# Sub_MCU.net
KiCad netlist of a schematic drawn in Altium Designer
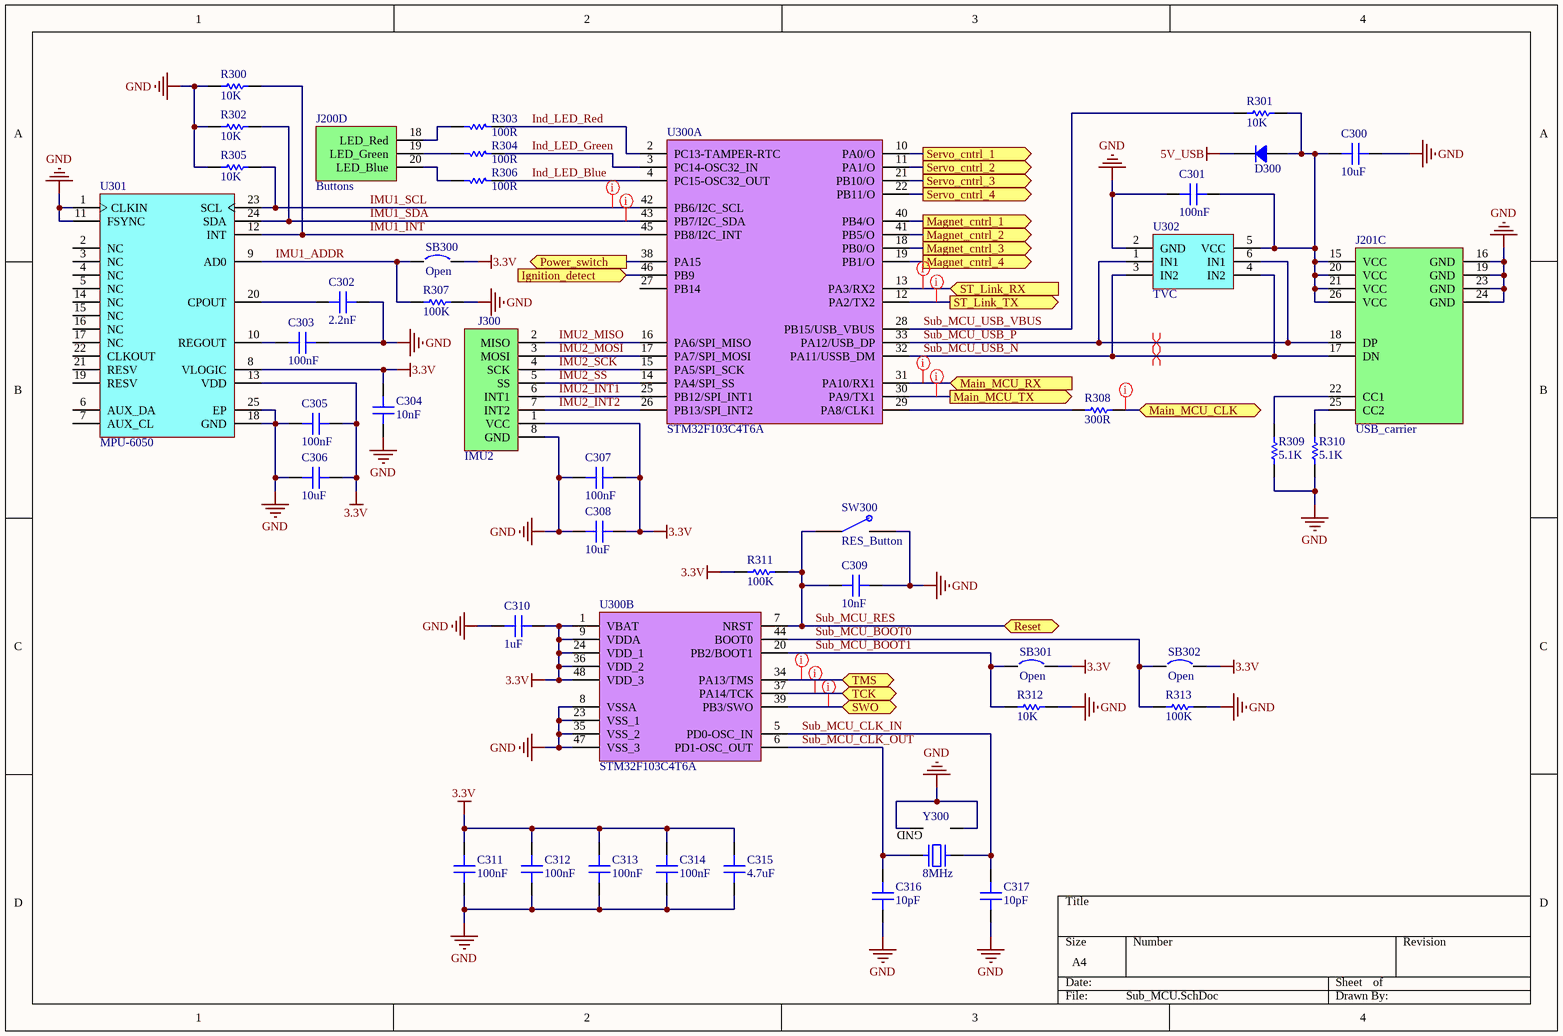
[diagram p0: Sub_MCU.SchDoc]

(export (version "E")
  (design (tool "Eeschema 10.0.6"))
  (components
    (comp (ref "C300")
      (value "10uF")
      (footprint "CAP 0603")
      (description "SMT Capacitor")
      (libsource (lib "Schlib1") (part "Capacitor"))
    )
    (comp (ref "C301")
      (value "100nF")
      (footprint "CAP 0603")
      (description "SMT Capacitor")
      (libsource (lib "Schlib1") (part "Capacitor"))
    )
    (comp (ref "C302")
      (value "2.2nF")
      (footprint "CAP 0603")
      (description "SMT Capacitor")
      (libsource (lib "Schlib1") (part "Capacitor"))
    )
    (comp (ref "C303")
      (value "100nF")
      (footprint "CAP 0603")
      (description "SMT Capacitor")
      (libsource (lib "Schlib1") (part "Capacitor"))
    )
    (comp (ref "C304")
      (value "10nF")
      (footprint "CAP 0603")
      (description "SMT Capacitor")
      (libsource (lib "Schlib1") (part "Capacitor"))
    )
    (comp (ref "C305")
      (value "100nF")
      (footprint "CAP 0603")
      (description "SMT Capacitor")
      (libsource (lib "Schlib1") (part "Capacitor"))
    )
    (comp (ref "C306")
      (value "10uF")
      (footprint "CAP 0603")
      (description "SMT Capacitor")
      (libsource (lib "Schlib1") (part "Capacitor"))
    )
    (comp (ref "C307")
      (value "100nF")
      (footprint "CAP 0603")
      (description "SMT Capacitor")
      (libsource (lib "Schlib1") (part "Capacitor"))
    )
    (comp (ref "C308")
      (value "10uF")
      (footprint "CAP 0603")
      (description "SMT Capacitor")
      (libsource (lib "Schlib1") (part "Capacitor"))
    )
    (comp (ref "C309")
      (value "10nF")
      (footprint "CAP 0603")
      (description "SMT Capacitor")
      (libsource (lib "Schlib1") (part "Capacitor"))
    )
    (comp (ref "C310")
      (value "1uF")
      (footprint "CAP 0603")
      (description "SMT Capacitor")
      (libsource (lib "Schlib1") (part "Capacitor"))
    )
    (comp (ref "C311")
      (value "100nF")
      (footprint "CAP 0603")
      (description "SMT Capacitor")
      (libsource (lib "Schlib1") (part "Capacitor"))
    )
    (comp (ref "C312")
      (value "100nF")
      (footprint "CAP 0603")
      (description "SMT Capacitor")
      (libsource (lib "Schlib1") (part "Capacitor"))
    )
    (comp (ref "C313")
      (value "100nF")
      (footprint "CAP 0603")
      (description "SMT Capacitor")
      (libsource (lib "Schlib1") (part "Capacitor"))
    )
    (comp (ref "C314")
      (value "100nF")
      (footprint "CAP 0603")
      (description "SMT Capacitor")
      (libsource (lib "Schlib1") (part "Capacitor"))
    )
    (comp (ref "C315")
      (value "4.7uF")
      (footprint "CAP 1206")
      (description "SMT Capacitor")
      (libsource (lib "Schlib1") (part "Capacitor"))
    )
    (comp (ref "C316")
      (value "10pF")
      (footprint "CAP 0603")
      (description "SMT Capacitor")
      (libsource (lib "Schlib1") (part "Capacitor"))
    )
    (comp (ref "C317")
      (value "10pF")
      (footprint "CAP 0603")
      (description "SMT Capacitor")
      (libsource (lib "Schlib1") (part "Capacitor"))
    )
    (comp (ref "D300")
      (value "~")
      (footprint "Bourns DO214AC SMA - duplicate")
      (description "Rectifier Diode")
      (libsource (lib "Schlib1") (part "Diode"))
    )
    (comp (ref "J200")
      (value "Buttons")
      (footprint "2167010409")
      (libsource (lib "Schlib1") (part "AUX_carrier"))
    )
    (comp (ref "J201")
      (value "USB_carrier")
      (footprint "2167010409")
      (libsource (lib "Schlib1") (part "USB_carrier"))
    )
    (comp (ref "J300")
      (value "IMU2")
      (footprint "SAMTEC_DWM-08-X-X-S-X")
      (libsource (lib "Schlib1") (part "IMU_connector"))
    )
    (comp (ref "R300")
      (value "10K")
      (footprint "RES 0603")
      (description "Resistor")
      (fields (field (name "PUBLISHER") "Altium Limited"))
      (libsource (lib "Schlib1") (part "Res"))
    )
    (comp (ref "R301")
      (value "10K")
      (footprint "RES 0603")
      (description "Resistor")
      (fields (field (name "PUBLISHER") "Altium Limited"))
      (libsource (lib "Schlib1") (part "Res"))
    )
    (comp (ref "R302")
      (value "10K")
      (footprint "RES 0603")
      (description "Resistor")
      (fields (field (name "PUBLISHER") "Altium Limited"))
      (libsource (lib "Schlib1") (part "Res"))
    )
    (comp (ref "R303")
      (value "100R")
      (footprint "RES 0603")
      (description "Resistor")
      (fields (field (name "PUBLISHER") "Altium Limited"))
      (libsource (lib "Schlib1") (part "Res"))
    )
    (comp (ref "R304")
      (value "100R")
      (footprint "RES 0603")
      (description "Resistor")
      (fields (field (name "PUBLISHER") "Altium Limited"))
      (libsource (lib "Schlib1") (part "Res"))
    )
    (comp (ref "R305")
      (value "10K")
      (footprint "RES 0603")
      (description "Resistor")
      (fields (field (name "PUBLISHER") "Altium Limited"))
      (libsource (lib "Schlib1") (part "Res"))
    )
    (comp (ref "R306")
      (value "100R")
      (footprint "RES 0603")
      (description "Resistor")
      (fields (field (name "PUBLISHER") "Altium Limited"))
      (libsource (lib "Schlib1") (part "Res"))
    )
    (comp (ref "R307")
      (value "100K")
      (footprint "RES 0603")
      (description "Resistor")
      (fields (field (name "PUBLISHER") "Altium Limited"))
      (libsource (lib "Schlib1") (part "Res"))
    )
    (comp (ref "R308")
      (value "300R")
      (footprint "RES 0603")
      (description "Resistor")
      (fields (field (name "PUBLISHER") "Altium Limited"))
      (libsource (lib "Schlib1") (part "Res"))
    )
    (comp (ref "R309")
      (value "5.1K")
      (footprint "RES 0603")
      (description "Resistor")
      (fields (field (name "PUBLISHER") "Altium Limited"))
      (libsource (lib "Schlib1") (part "Res"))
    )
    (comp (ref "R310")
      (value "5.1K")
      (footprint "RES 0603")
      (description "Resistor")
      (fields (field (name "PUBLISHER") "Altium Limited"))
      (libsource (lib "Schlib1") (part "Res"))
    )
    (comp (ref "R311")
      (value "100K")
      (footprint "RES 0603")
      (description "Resistor")
      (fields (field (name "PUBLISHER") "Altium Limited"))
      (libsource (lib "Schlib1") (part "Res"))
    )
    (comp (ref "R312")
      (value "10K")
      (footprint "RES 0603")
      (description "Resistor")
      (fields (field (name "PUBLISHER") "Altium Limited"))
      (libsource (lib "Schlib1") (part "Res"))
    )
    (comp (ref "R313")
      (value "100K")
      (footprint "RES 0603")
      (description "Resistor")
      (fields (field (name "PUBLISHER") "Altium Limited"))
      (libsource (lib "Schlib1") (part "Res"))
    )
    (comp (ref "SB300")
      (value "Open")
      (footprint "SB_0603")
      (description "Circuit Breaker")
      (fields (field (name "PUBLISHER") "Altium Limited"))
      (libsource (lib "Schlib1") (part "Circuit Breaker"))
    )
    (comp (ref "SB301")
      (value "Open")
      (footprint "SB_0603")
      (description "Circuit Breaker")
      (fields (field (name "PUBLISHER") "Altium Limited"))
      (libsource (lib "Schlib1") (part "Circuit Breaker"))
    )
    (comp (ref "SB302")
      (value "Open")
      (footprint "SB_0603")
      (description "Circuit Breaker")
      (fields (field (name "PUBLISHER") "Altium Limited"))
      (libsource (lib "Schlib1") (part "Circuit Breaker"))
    )
    (comp (ref "SW300")
      (value "RES_Button")
      (footprint "PTS636SM50JSMTRLFS")
      (libsource (lib "Schlib1") (part "RES_Button"))
    )
    (comp (ref "U300")
      (value "STM32F103C4T6A")
      (footprint "TI PQFP-48 PAG0048A")
      (libsource (lib "") (part "CMP-0237-00255-3_1"))
    )
    (comp (ref "U301")
      (value "MPU-6050")
      (footprint "IS-QFN-24_V")
      (fields (field (name "MANUFACTURER") "InvenSense"))
      (libsource (lib "Schlib1") (part "CMP-1753-00002-2"))
    )
    (comp (ref "U302")
      (value "TVC")
      (footprint "ECEN_1400:DIODES SOT-23-6 W6")
      (libsource (lib "Schlib1") (part "USB_TVC_protection"))
    )
    (comp (ref "Y300")
      (value "8MHz")
      (footprint "XTAL_ECS-80-10-33-CHN-TR3")
      (description "SMT Crystal")
      (libsource (lib "Schlib1") (part "Crystal 8Mhz"))
    )
  )
  (nets
    (net (code "1") (name "/IMU1_ADDR") (class "Default")
      (node (ref "R307") (pin "2") (pinfunction "2_2") (pintype "passive"))
      (node (ref "SB300") (pin "1") (pinfunction "1_1") (pintype "passive"))
      (node (ref "U301") (pin "9") (pinfunction "AD0_9") (pintype "passive"))
    )
    (net (code "2") (name "/IMU1_INT") (class "Default")
      (node (ref "R300") (pin "1") (pinfunction "1_1") (pintype "passive"))
      (node (ref "U300") (pin "45") (pinfunction "PB8/I2C_INT_45") (pintype "passive"))
      (node (ref "U301") (pin "12") (pinfunction "INT_12") (pintype "passive"))
    )
    (net (code "3") (name "/IMU1_SCL") (class "Default")
      (node (ref "R305") (pin "1") (pinfunction "1_1") (pintype "passive"))
      (node (ref "U300") (pin "42") (pinfunction "PB6/I2C_SCL_42") (pintype "passive"))
      (node (ref "U301") (pin "23") (pinfunction "SCL_23") (pintype "passive"))
    )
    (net (code "4") (name "/IMU1_SDA") (class "Default")
      (node (ref "R302") (pin "1") (pinfunction "1_1") (pintype "passive"))
      (node (ref "U300") (pin "43") (pinfunction "PB7/I2C_SDA_43") (pintype "passive"))
      (node (ref "U301") (pin "24") (pinfunction "SDA_24") (pintype "passive"))
    )
    (net (code "5") (name "/IMU2_INT1") (class "Default")
      (node (ref "J300") (pin "6") (pinfunction "INT1_6") (pintype "passive"))
      (node (ref "U300") (pin "25") (pinfunction "PB12/SPI_INT1_25") (pintype "passive"))
    )
    (net (code "6") (name "/IMU2_INT2") (class "Default")
      (node (ref "J300") (pin "7") (pinfunction "INT2_7") (pintype "passive"))
      (node (ref "U300") (pin "26") (pinfunction "PB13/SPI_INT2_26") (pintype "passive"))
    )
    (net (code "7") (name "/IMU2_MISO") (class "Default")
      (node (ref "J300") (pin "2") (pinfunction "MISO_2") (pintype "passive"))
      (node (ref "U300") (pin "16") (pinfunction "PA6/SPI_MISO_16") (pintype "passive"))
    )
    (net (code "8") (name "/IMU2_MOSI") (class "Default")
      (node (ref "J300") (pin "3") (pinfunction "MOSI_3") (pintype "passive"))
      (node (ref "U300") (pin "17") (pinfunction "PA7/SPI_MOSI_17") (pintype "passive"))
    )
    (net (code "9") (name "/IMU2_SCK") (class "Default")
      (node (ref "J300") (pin "4") (pinfunction "SCK_4") (pintype "passive"))
      (node (ref "U300") (pin "15") (pinfunction "PA5/SPI_SCK_15") (pintype "passive"))
    )
    (net (code "10") (name "/IMU2_SS") (class "Default")
      (node (ref "J300") (pin "5") (pinfunction "SS_5") (pintype "passive"))
      (node (ref "U300") (pin "14") (pinfunction "PA4/SPI_SS_14") (pintype "passive"))
    )
    (net (code "11") (name "/Ignition_detect") (class "Default")
      (node (ref "U300") (pin "46") (pinfunction "PB9_46") (pintype "passive"))
    )
    (net (code "12") (name "/Ind_LED_Blue") (class "Default")
      (node (ref "R306") (pin "2") (pinfunction "2_2") (pintype "passive"))
      (node (ref "U300") (pin "4") (pinfunction "PC15-OSC32_OUT_4") (pintype "passive"))
    )
    (net (code "13") (name "/Ind_LED_Green") (class "Default")
      (node (ref "R304") (pin "2") (pinfunction "2_2") (pintype "passive"))
      (node (ref "U300") (pin "3") (pinfunction "PC14-OSC32_IN_3") (pintype "passive"))
    )
    (net (code "14") (name "/Ind_LED_Red") (class "Default")
      (node (ref "R303") (pin "2") (pinfunction "2_2") (pintype "passive"))
      (node (ref "U300") (pin "2") (pinfunction "PC13-TAMPER-RTC_2") (pintype "passive"))
    )
    (net (code "15") (name "/Magnet_cntrl_1") (class "Default")
      (node (ref "U300") (pin "40") (pinfunction "PB4/O_40") (pintype "passive"))
    )
    (net (code "16") (name "/Magnet_cntrl_2") (class "Default")
      (node (ref "U300") (pin "41") (pinfunction "PB5/O_41") (pintype "passive"))
    )
    (net (code "17") (name "/Magnet_cntrl_3") (class "Default")
      (node (ref "U300") (pin "18") (pinfunction "PB0/O_18") (pintype "passive"))
    )
    (net (code "18") (name "/Magnet_cntrl_4") (class "Default")
      (node (ref "U300") (pin "19") (pinfunction "PB1/O_19") (pintype "passive"))
    )
    (net (code "19") (name "/Main_MCU_CLK") (class "Default")
      (node (ref "R308") (pin "1") (pinfunction "1_1") (pintype "passive"))
    )
    (net (code "20") (name "/Main_MCU_RX") (class "Default")
      (node (ref "U300") (pin "31") (pinfunction "PA10/RX1_31") (pintype "passive"))
    )
    (net (code "21") (name "/Main_MCU_TX") (class "Default")
      (node (ref "U300") (pin "30") (pinfunction "PA9/TX1_30") (pintype "passive"))
    )
    (net (code "22") (name "/Power_switch") (class "Default")
      (node (ref "U300") (pin "38") (pinfunction "PA15_38") (pintype "passive"))
    )
    (net (code "23") (name "/ST_Link_RX") (class "Default")
      (node (ref "U300") (pin "13") (pinfunction "PA3/RX2_13") (pintype "passive"))
    )
    (net (code "24") (name "/ST_Link_TX") (class "Default")
      (node (ref "U300") (pin "12") (pinfunction "PA2/TX2_12") (pintype "passive"))
    )
    (net (code "25") (name "/SWO") (class "Default")
      (node (ref "U300") (pin "39") (pinfunction "PB3/SWO_39") (pintype "passive"))
    )
    (net (code "26") (name "/Servo_cntrl_1") (class "Default")
      (node (ref "U300") (pin "10") (pinfunction "PA0/O_10") (pintype "passive"))
    )
    (net (code "27") (name "/Servo_cntrl_2") (class "Default")
      (node (ref "U300") (pin "11") (pinfunction "PA1/O_11") (pintype "passive"))
    )
    (net (code "28") (name "/Servo_cntrl_3") (class "Default")
      (node (ref "U300") (pin "21") (pinfunction "PB10/O_21") (pintype "passive"))
    )
    (net (code "29") (name "/Servo_cntrl_4") (class "Default")
      (node (ref "U300") (pin "22") (pinfunction "PB11/O_22") (pintype "passive"))
    )
    (net (code "30") (name "/Sub_MCU_BOOT0") (class "Default")
      (node (ref "R313") (pin "2") (pinfunction "2_2") (pintype "passive"))
      (node (ref "SB302") (pin "1") (pinfunction "1_1") (pintype "passive"))
      (node (ref "U300") (pin "44") (pinfunction "BOOT0_44") (pintype "passive"))
    )
    (net (code "31") (name "/Sub_MCU_BOOT1") (class "Default")
      (node (ref "R312") (pin "2") (pinfunction "2_2") (pintype "passive"))
      (node (ref "SB301") (pin "1") (pinfunction "1_1") (pintype "passive"))
      (node (ref "U300") (pin "20") (pinfunction "PB2/BOOT1_20") (pintype "passive"))
    )
    (net (code "32") (name "/Sub_MCU_CLK_IN") (class "Default")
      (node (ref "C317") (pin "2") (pinfunction "2_2") (pintype "passive"))
      (node (ref "U300") (pin "5") (pinfunction "PD0-OSC_IN_5") (pintype "passive"))
      (node (ref "Y300") (pin "3") (pinfunction "3_3") (pintype "passive"))
    )
    (net (code "33") (name "/Sub_MCU_CLK_OUT") (class "Default")
      (node (ref "C316") (pin "2") (pinfunction "2_2") (pintype "passive"))
      (node (ref "U300") (pin "6") (pinfunction "PD1-OSC_OUT_6") (pintype "passive"))
      (node (ref "Y300") (pin "1") (pinfunction "1_1") (pintype "passive"))
    )
    (net (code "34") (name "/Sub_MCU_RES") (class "Default")
      (node (ref "C309") (pin "2") (pinfunction "2_2") (pintype "passive"))
      (node (ref "R311") (pin "1") (pinfunction "1_1") (pintype "passive"))
      (node (ref "SW300") (pin "1") (pinfunction "1_1") (pintype "passive"))
      (node (ref "U300") (pin "7") (pinfunction "NRST_7") (pintype "passive"))
    )
    (net (code "35") (name "/Sub_MCU_USB_N") (class "Default")
      (node (ref "J201") (pin "17") (pinfunction "DN_17") (pintype "passive"))
      (node (ref "U300") (pin "32") (pinfunction "PA11/USSB_DM_32") (pintype "passive"))
      (node (ref "U302") (pin "3") (pinfunction "IN2_3") (pintype "passive"))
      (node (ref "U302") (pin "4") (pinfunction "IN2_4") (pintype "passive"))
    )
    (net (code "36") (name "/Sub_MCU_USB_P") (class "Default")
      (node (ref "J201") (pin "18") (pinfunction "DP_18") (pintype "passive"))
      (node (ref "U300") (pin "33") (pinfunction "PA12/USB_DP_33") (pintype "passive"))
      (node (ref "U302") (pin "1") (pinfunction "IN1_1") (pintype "passive"))
      (node (ref "U302") (pin "6") (pinfunction "IN1_6") (pintype "passive"))
    )
    (net (code "37") (name "/Sub_MCU_USB_VBUS") (class "Default")
      (node (ref "R301") (pin "2") (pinfunction "2_2") (pintype "passive"))
      (node (ref "U300") (pin "28") (pinfunction "PB15/USB_VBUS_28") (pintype "passive"))
    )
    (net (code "38") (name "/TCK") (class "Default")
      (node (ref "U300") (pin "37") (pinfunction "PA14/TCK_37") (pintype "passive"))
    )
    (net (code "39") (name "/TMS") (class "Default")
      (node (ref "U300") (pin "34") (pinfunction "PA13/TMS_34") (pintype "passive"))
    )
    (net (code "40") (name "3.3V") (class "Default")
      (node (ref "C304") (pin "1") (pinfunction "1_1") (pintype "passive"))
      (node (ref "C305") (pin "2") (pinfunction "2_2") (pintype "passive"))
      (node (ref "C306") (pin "2") (pinfunction "2_2") (pintype "passive"))
      (node (ref "C307") (pin "2") (pinfunction "2_2") (pintype "passive"))
      (node (ref "C308") (pin "2") (pinfunction "2_2") (pintype "passive"))
      (node (ref "C310") (pin "2") (pinfunction "2_2") (pintype "passive"))
      (node (ref "C311") (pin "2") (pinfunction "2_2") (pintype "passive"))
      (node (ref "C312") (pin "2") (pinfunction "2_2") (pintype "passive"))
      (node (ref "C313") (pin "2") (pinfunction "2_2") (pintype "passive"))
      (node (ref "C314") (pin "2") (pinfunction "2_2") (pintype "passive"))
      (node (ref "C315") (pin "2") (pinfunction "2_2") (pintype "passive"))
      (node (ref "J300") (pin "1") (pinfunction "VCC_1") (pintype "passive"))
      (node (ref "R311") (pin "2") (pinfunction "2_2") (pintype "passive"))
      (node (ref "SB300") (pin "2") (pinfunction "2_2") (pintype "passive"))
      (node (ref "SB301") (pin "2") (pinfunction "2_2") (pintype "passive"))
      (node (ref "SB302") (pin "2") (pinfunction "2_2") (pintype "passive"))
      (node (ref "U300") (pin "1") (pinfunction "VBAT_1") (pintype "power_in"))
      (node (ref "U300") (pin "24") (pinfunction "VDD_1_24") (pintype "power_in"))
      (node (ref "U300") (pin "36") (pinfunction "VDD_2_36") (pintype "power_in"))
      (node (ref "U300") (pin "48") (pinfunction "VDD_3_48") (pintype "power_in"))
      (node (ref "U300") (pin "9") (pinfunction "VDDA_9") (pintype "power_in"))
      (node (ref "U301") (pin "13") (pinfunction "VDD_13") (pintype "passive"))
      (node (ref "U301") (pin "8") (pinfunction "VLOGIC_8") (pintype "passive"))
    )
    (net (code "41") (name "5V_USB") (class "Default")
      (node (ref "D300") (pin "2") (pinfunction "2_2") (pintype "passive"))
    )
    (net (code "42") (name "GND") (class "Default")
      (node (ref "C300") (pin "2") (pinfunction "2_2") (pintype "passive"))
      (node (ref "C301") (pin "1") (pinfunction "1_1") (pintype "passive"))
      (node (ref "C302") (pin "2") (pinfunction "2_2") (pintype "passive"))
      (node (ref "C303") (pin "2") (pinfunction "2_2") (pintype "passive"))
      (node (ref "C304") (pin "2") (pinfunction "2_2") (pintype "passive"))
      (node (ref "C305") (pin "1") (pinfunction "1_1") (pintype "passive"))
      (node (ref "C306") (pin "1") (pinfunction "1_1") (pintype "passive"))
      (node (ref "C307") (pin "1") (pinfunction "1_1") (pintype "passive"))
      (node (ref "C308") (pin "1") (pinfunction "1_1") (pintype "passive"))
      (node (ref "C309") (pin "1") (pinfunction "1_1") (pintype "passive"))
      (node (ref "C310") (pin "1") (pinfunction "1_1") (pintype "passive"))
      (node (ref "C311") (pin "1") (pinfunction "1_1") (pintype "passive"))
      (node (ref "C312") (pin "1") (pinfunction "1_1") (pintype "passive"))
      (node (ref "C313") (pin "1") (pinfunction "1_1") (pintype "passive"))
      (node (ref "C314") (pin "1") (pinfunction "1_1") (pintype "passive"))
      (node (ref "C315") (pin "1") (pinfunction "1_1") (pintype "passive"))
      (node (ref "C316") (pin "1") (pinfunction "1_1") (pintype "passive"))
      (node (ref "C317") (pin "1") (pinfunction "1_1") (pintype "passive"))
      (node (ref "J201") (pin "16") (pinfunction "GND_16") (pintype "passive"))
      (node (ref "J201") (pin "19") (pinfunction "GND_19") (pintype "passive"))
      (node (ref "J201") (pin "23") (pinfunction "GND_23") (pintype "passive"))
      (node (ref "J201") (pin "24") (pinfunction "GND_24") (pintype "passive"))
      (node (ref "J300") (pin "8") (pinfunction "GND_8") (pintype "passive"))
      (node (ref "R300") (pin "2") (pinfunction "2_2") (pintype "passive"))
      (node (ref "R302") (pin "2") (pinfunction "2_2") (pintype "passive"))
      (node (ref "R305") (pin "2") (pinfunction "2_2") (pintype "passive"))
      (node (ref "R307") (pin "1") (pinfunction "1_1") (pintype "passive"))
      (node (ref "R309") (pin "1") (pinfunction "1_1") (pintype "passive"))
      (node (ref "R310") (pin "1") (pinfunction "1_1") (pintype "passive"))
      (node (ref "R312") (pin "1") (pinfunction "1_1") (pintype "passive"))
      (node (ref "R313") (pin "1") (pinfunction "1_1") (pintype "passive"))
      (node (ref "SW300") (pin "2") (pinfunction "2_2") (pintype "passive"))
      (node (ref "U300") (pin "23") (pinfunction "VSS_1_23") (pintype "power_in"))
      (node (ref "U300") (pin "35") (pinfunction "VSS_2_35") (pintype "power_in"))
      (node (ref "U300") (pin "47") (pinfunction "VSS_3_47") (pintype "power_in"))
      (node (ref "U300") (pin "8") (pinfunction "VSSA_8") (pintype "power_in"))
      (node (ref "U301") (pin "1") (pinfunction "CLKIN_1") (pintype "passive"))
      (node (ref "U301") (pin "11") (pinfunction "FSYNC_11") (pintype "passive"))
      (node (ref "U301") (pin "18") (pinfunction "GND_18") (pintype "passive"))
      (node (ref "U301") (pin "25") (pinfunction "EP_25") (pintype "passive"))
      (node (ref "U302") (pin "2") (pinfunction "GND_2") (pintype "passive"))
      (node (ref "Y300") (pin "2") (pinfunction "GND_2") (pintype "passive"))
      (node (ref "Y300") (pin "4") (pinfunction "GND_4") (pintype "passive"))
    )
    (net (code "43") (name "Net-(J200D-LED_Blue)") (class "Default")
      (node (ref "J200") (pin "20") (pinfunction "LED_Blue_20") (pintype "passive"))
      (node (ref "R306") (pin "1") (pinfunction "1_1") (pintype "passive"))
    )
    (net (code "44") (name "Net-(J200D-LED_Green)") (class "Default")
      (node (ref "J200") (pin "19") (pinfunction "LED_Green_19") (pintype "passive"))
      (node (ref "R304") (pin "1") (pinfunction "1_1") (pintype "passive"))
    )
    (net (code "45") (name "Net-(J200D-LED_Red)") (class "Default")
      (node (ref "J200") (pin "18") (pinfunction "LED_Red_18") (pintype "passive"))
      (node (ref "R303") (pin "1") (pinfunction "1_1") (pintype "passive"))
    )
    (net (code "46") (name "Net-(J201C-CC1)") (class "Default")
      (node (ref "J201") (pin "22") (pinfunction "CC1_22") (pintype "passive"))
      (node (ref "R309") (pin "2") (pinfunction "2_2") (pintype "passive"))
    )
    (net (code "47") (name "Net-(J201C-CC2)") (class "Default")
      (node (ref "J201") (pin "25") (pinfunction "CC2_25") (pintype "passive"))
      (node (ref "R310") (pin "2") (pinfunction "2_2") (pintype "passive"))
    )
    (net (code "48") (name "Net-(U300A-PA8{slash}CLK1)") (class "Default")
      (node (ref "R308") (pin "2") (pinfunction "2_2") (pintype "passive"))
      (node (ref "U300") (pin "29") (pinfunction "PA8/CLK1_29") (pintype "passive"))
    )
    (net (code "49") (name "Net-(U301-CPOUT)") (class "Default")
      (node (ref "C302") (pin "1") (pinfunction "1_1") (pintype "passive"))
      (node (ref "U301") (pin "20") (pinfunction "CPOUT_20") (pintype "passive"))
    )
    (net (code "50") (name "Net-(U301-REGOUT)") (class "Default")
      (node (ref "C303") (pin "1") (pinfunction "1_1") (pintype "passive"))
      (node (ref "U301") (pin "10") (pinfunction "REGOUT_10") (pintype "passive"))
    )
    (net (code "51") (name "Net-(U302-VCC)") (class "Default")
      (node (ref "C300") (pin "1") (pinfunction "1_1") (pintype "passive"))
      (node (ref "C301") (pin "2") (pinfunction "2_2") (pintype "passive"))
      (node (ref "D300") (pin "1") (pinfunction "1_1") (pintype "passive"))
      (node (ref "J201") (pin "15") (pinfunction "VCC_15") (pintype "passive"))
      (node (ref "J201") (pin "20") (pinfunction "VCC_20") (pintype "passive"))
      (node (ref "J201") (pin "21") (pinfunction "VCC_21") (pintype "passive"))
      (node (ref "J201") (pin "26") (pinfunction "VCC_26") (pintype "passive"))
      (node (ref "R301") (pin "1") (pinfunction "1_1") (pintype "passive"))
      (node (ref "U302") (pin "5") (pinfunction "VCC_5") (pintype "passive"))
    )
    (net (code "52") (name "unconnected-(U300A-PB14-Pad27)") (class "Default")
      (node (ref "U300") (pin "27") (pinfunction "PB14_27") (pintype "passive"))
    )
    (net (code "53") (name "unconnected-(U301-AUX_CL-Pad7)") (class "Default")
      (node (ref "U301") (pin "7") (pinfunction "AUX_CL_7") (pintype "passive"))
    )
    (net (code "54") (name "unconnected-(U301-AUX_DA-Pad6)") (class "Default")
      (node (ref "U301") (pin "6") (pinfunction "AUX_DA_6") (pintype "passive"))
    )
    (net (code "55") (name "unconnected-(U301-CLKOUT-Pad22)") (class "Default")
      (node (ref "U301") (pin "22") (pinfunction "CLKOUT_22") (pintype "passive"))
    )
    (net (code "56") (name "unconnected-(U301-NC-Pad2)") (class "Default")
      (node (ref "U301") (pin "2") (pinfunction "NC_2") (pintype "passive"))
    )
    (net (code "57") (name "unconnected-(U301-NC-Pad3)") (class "Default")
      (node (ref "U301") (pin "3") (pinfunction "NC_3") (pintype "passive"))
    )
    (net (code "58") (name "unconnected-(U301-NC-Pad4)") (class "Default")
      (node (ref "U301") (pin "4") (pinfunction "NC_4") (pintype "passive"))
    )
    (net (code "59") (name "unconnected-(U301-NC-Pad5)") (class "Default")
      (node (ref "U301") (pin "5") (pinfunction "NC_5") (pintype "passive"))
    )
    (net (code "60") (name "unconnected-(U301-NC-Pad14)") (class "Default")
      (node (ref "U301") (pin "14") (pinfunction "NC_14") (pintype "passive"))
    )
    (net (code "61") (name "unconnected-(U301-NC-Pad15)") (class "Default")
      (node (ref "U301") (pin "15") (pinfunction "NC_15") (pintype "passive"))
    )
    (net (code "62") (name "unconnected-(U301-NC-Pad16)") (class "Default")
      (node (ref "U301") (pin "16") (pinfunction "NC_16") (pintype "passive"))
    )
    (net (code "63") (name "unconnected-(U301-NC-Pad17)") (class "Default")
      (node (ref "U301") (pin "17") (pinfunction "NC_17") (pintype "passive"))
    )
    (net (code "64") (name "unconnected-(U301-RESV-Pad19)") (class "Default")
      (node (ref "U301") (pin "19") (pinfunction "RESV_19") (pintype "passive"))
    )
    (net (code "65") (name "unconnected-(U301-RESV-Pad21)") (class "Default")
      (node (ref "U301") (pin "21") (pinfunction "RESV_21") (pintype "passive"))
    )
  )
)
